# ADC-Buzzer.net
KiCad netlist of a schematic drawn in Altium Designer
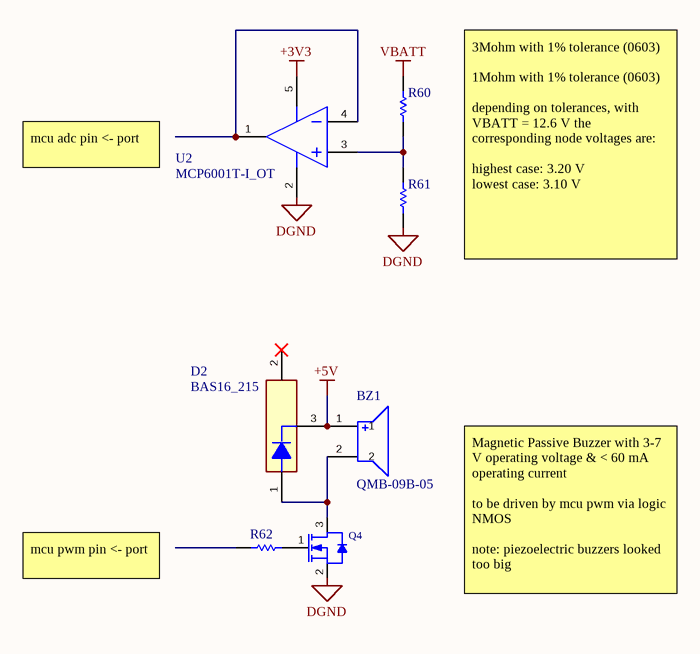
[diagram p0: ADC-Buzzer.SchDoc]

(export (version "E")
  (design (tool "Eeschema 10.0.6"))
  (components
    (comp (ref "BZ1")
      (value "QMB-09B-05")
      (footprint "QMB-09B-05")
      (fields (field (name "LCSC PART #") "C161819"))
      (libsource (lib "flight-controller") (part "QMB-09B-05"))
    )
    (comp (ref "D2")
      (value "BAS16_215")
      (footprint "BAS16_215")
      (description "1.25V@150mA 100V 215mA 250mW 4A 4ns 500nA@80V Independent SOT-23 Switching Diodes ROHS")
      (fields (field (name "LCSC PART #") "C79997") (field (name "MANU PART #") "BAS16,215"))
      (libsource (lib "flight-controller") (part "BAS16_215"))
    )
    (comp (ref "Q4")
      (value "IRLML6344TRPBF-ES")
      (footprint "IRLML6344TRPBF-ES")
      (fields (field (name "LCSC PART #") "C21713845"))
      (libsource (lib "flight-controller") (part "IRLML6344TRPBF-ES"))
    )
    (comp (ref "R60")
      (value "FRC0603F3004TS")
      (footprint "FRC0603F3004TS")
      (description "-55℃~+155℃ 100mW 3MΩ 75V Thick Film Resistor ±1% ±100ppm/℃ 0603 Chip Resistor - Surface Mount ROHS")
      (fields (field (name "LCSC PART #") "C2930149"))
      (libsource (lib "flight-controller") (part "FRC0603F3004TS"))
    )
    (comp (ref "R61")
      (value "RC0603FR-071ML")
      (footprint "RC0603FR-071ML")
      (description "-55℃~+155℃ 100mW 1MΩ 75V Thick Film Resistor ±1% ±100ppm/℃ 0603 Chip Resistor - Surface Mount ROHS")
      (fields (field (name "LCSC PART #") "C105578"))
      (libsource (lib "flight-controller") (part "RC0603FR-071ML"))
    )
    (comp (ref "R62")
      (value "RC0603FR-0710RL")
      (footprint "RC0603FR-071ML")
      (description "-55℃~+155℃ 100mW 10Ω 75V Thick Film Resistor ±1% ±200ppm/℃ 0603 Chip Resistor - Surface Mount ROHS")
      (fields (field (name "LCSC PART #") "C109318"))
      (libsource (lib "flight-controller") (part "RC0603FR-0710RL"))
    )
    (comp (ref "U2")
      (value "MCP6001T-I_OT")
      (footprint "MCP6001T-I_OT")
      (fields (field (name "LCSC PART #") "C116490") (field (name "MANU PART #") "MCP6001T-I/OT"))
      (libsource (lib "flight-controller") (part "MCP6001T-I_OT"))
    )
  )
  (nets
    (net (code "1") (name "+3V3") (class "Default")
      (node (ref "U2") (pin "5") (pinfunction "VDD_5") (pintype "passive"))
    )
    (net (code "2") (name "+5V") (class "Default")
      (node (ref "BZ1") (pin "1") (pinfunction "1_1") (pintype "passive"))
      (node (ref "D2") (pin "3") (pinfunction "3_3") (pintype "passive"))
    )
    (net (code "3") (name "DGND") (class "Default")
      (node (ref "Q4") (pin "2") (pinfunction "S_2") (pintype "passive"))
      (node (ref "R61") (pin "1") (pinfunction "1_1") (pintype "passive"))
      (node (ref "U2") (pin "2") (pinfunction "VSS_2") (pintype "passive"))
    )
    (net (code "4") (name "Net-(Q4-D)") (class "Default")
      (node (ref "BZ1") (pin "2") (pinfunction "2_2") (pintype "passive"))
      (node (ref "D2") (pin "1") (pinfunction "1_1") (pintype "passive"))
      (node (ref "Q4") (pin "3") (pinfunction "D_3") (pintype "passive"))
    )
    (net (code "5") (name "Net-(Q4-G)") (class "Default")
      (node (ref "Q4") (pin "1") (pinfunction "G_1") (pintype "passive"))
      (node (ref "R62") (pin "2") (pinfunction "2_2") (pintype "passive"))
    )
    (net (code "6") (name "Net-(U2-VIN+)") (class "Default")
      (node (ref "R60") (pin "1") (pinfunction "1_1") (pintype "passive"))
      (node (ref "R61") (pin "2") (pinfunction "2_2") (pintype "passive"))
      (node (ref "U2") (pin "3") (pinfunction "VIN+_3") (pintype "passive"))
    )
    (net (code "7") (name "Net-(U2-VIN-)") (class "Default")
      (node (ref "U2") (pin "1") (pinfunction "VOUT_1") (pintype "passive"))
      (node (ref "U2") (pin "4") (pinfunction "VIN-_4") (pintype "passive"))
    )
    (net (code "8") (name "VBATT") (class "Default")
      (node (ref "R60") (pin "2") (pinfunction "2_2") (pintype "passive"))
    )
    (net (code "9") (name "unconnected-(D2-Pad2)") (class "Default")
      (node (ref "D2") (pin "2") (pinfunction "2_2") (pintype "passive+no_connect"))
    )
    (net (code "10") (name "unconnected-(R62-Pad1)") (class "Default")
      (node (ref "R62") (pin "1") (pinfunction "1_1") (pintype "passive"))
    )
  )
)
